# 04-POWERV2_4.net
KiCad netlist of a schematic drawn in Altium Designer
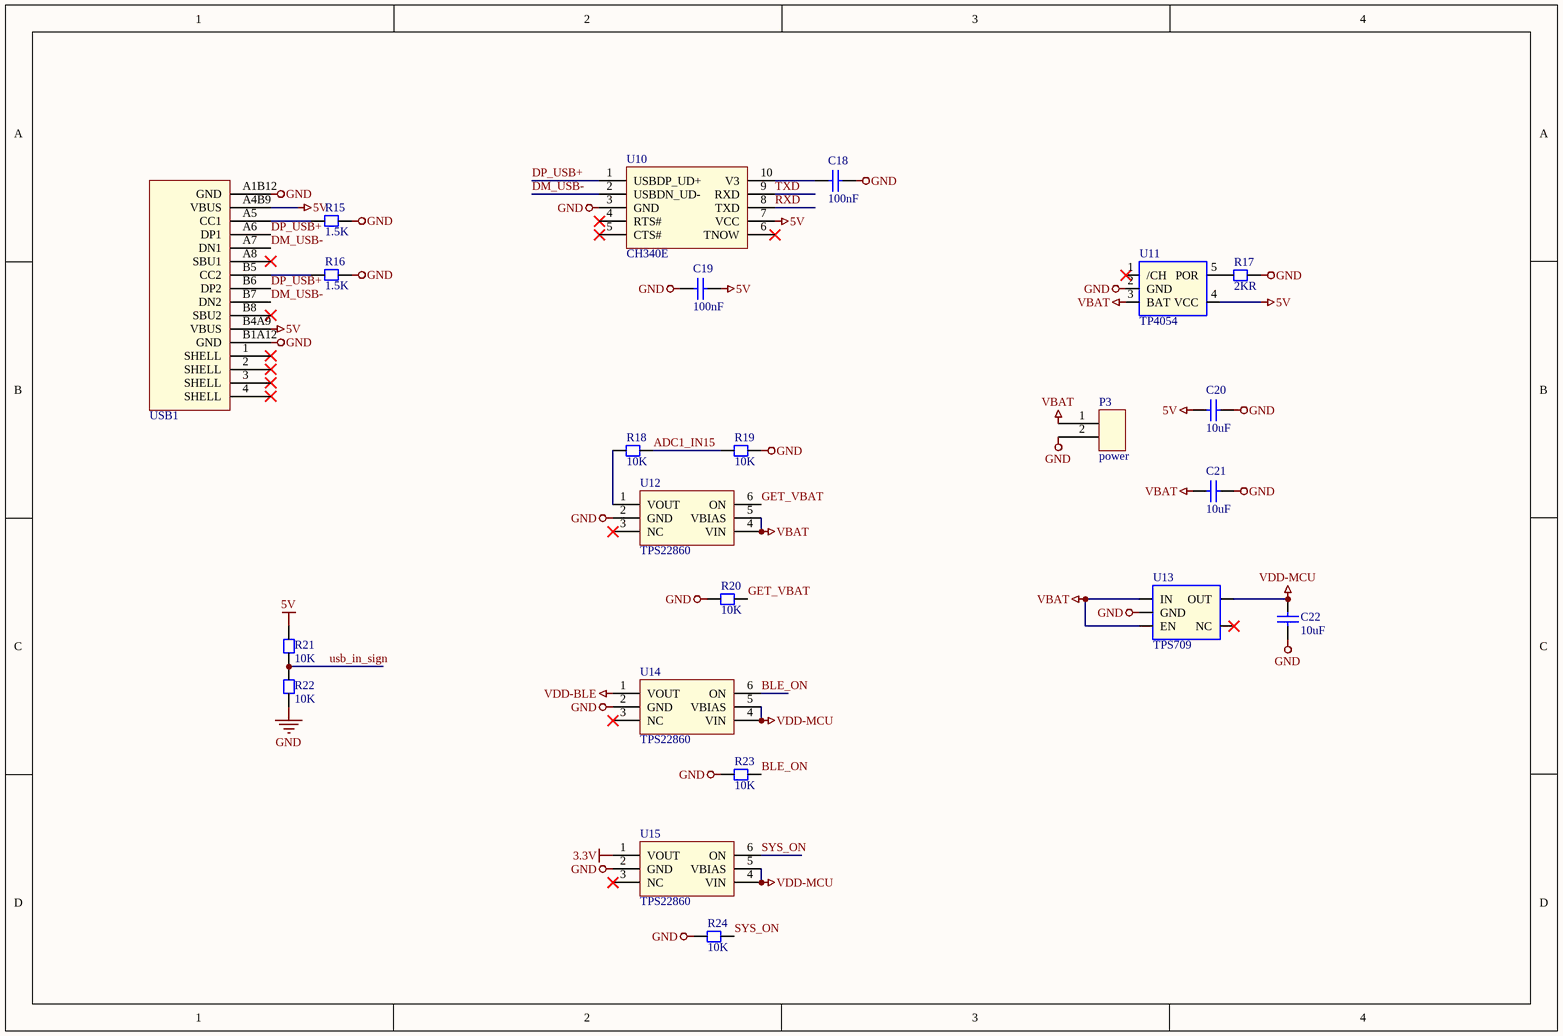
[diagram p0: 04-POWERV2.4.SchDoc]

(export (version "E")
  (design (tool "Eeschema 10.0.6"))
  (components
    (comp (ref "C18")
      (value "100nF")
      (footprint "CC1005-0402")
      (description "贴片电容")
      (libsource (lib "tianxiaohua_Schlib") (part "Chip capacitor"))
    )
    (comp (ref "C19")
      (value "100nF")
      (footprint "CC1005-0402")
      (description "贴片电容")
      (libsource (lib "tianxiaohua_Schlib") (part "Chip capacitor"))
    )
    (comp (ref "C20")
      (value "10uF")
      (footprint "CC1005-0402")
      (description "贴片电容")
      (libsource (lib "tianxiaohua_Schlib") (part "Chip capacitor"))
    )
    (comp (ref "C21")
      (value "10uF")
      (footprint "CC1005-0402")
      (description "贴片电容")
      (libsource (lib "tianxiaohua_Schlib") (part "Chip capacitor"))
    )
    (comp (ref "C22")
      (value "10uF")
      (footprint "CC1005-0402")
      (description "贴片电容")
      (libsource (lib "tianxiaohua_Schlib") (part "Chip capacitor"))
    )
    (comp (ref "P3")
      (value "power")
      (footprint "POWER-3.7V")
      (libsource (lib "tianxiaohua_Schlib") (part "power"))
    )
    (comp (ref "R15")
      (value "1.5K")
      (footprint "CR1005-0402")
      (description "贴片电阻")
      (libsource (lib "tianxiaohua_Schlib") (part "Chip resistor"))
    )
    (comp (ref "R16")
      (value "1.5K")
      (footprint "CR1005-0402")
      (description "贴片电阻")
      (libsource (lib "tianxiaohua_Schlib") (part "Chip resistor"))
    )
    (comp (ref "R17")
      (value "2KR")
      (footprint "CR1005-0402")
      (description "贴片电阻")
      (libsource (lib "tianxiaohua_Schlib") (part "Chip resistor"))
    )
    (comp (ref "R18")
      (value "10K")
      (footprint "CR1005-0402")
      (description "贴片电阻")
      (libsource (lib "tianxiaohua_Schlib") (part "Chip resistor"))
    )
    (comp (ref "R19")
      (value "10K")
      (footprint "CR1005-0402")
      (description "贴片电阻")
      (libsource (lib "") (part "Chip resistor_1"))
    )
    (comp (ref "R20")
      (value "10K")
      (footprint "CR1005-0402")
      (description "贴片电阻")
      (libsource (lib "") (part "Chip resistor_1"))
    )
    (comp (ref "R21")
      (value "10K")
      (footprint "CR1005-0402")
      (description "贴片电阻")
      (libsource (lib "") (part "Chip resistor_2"))
    )
    (comp (ref "R22")
      (value "10K")
      (footprint "CR1005-0402")
      (description "贴片电阻")
      (libsource (lib "") (part "Chip resistor_2"))
    )
    (comp (ref "R23")
      (value "10K")
      (footprint "CR1005-0402")
      (description "贴片电阻")
      (libsource (lib "") (part "Chip resistor_1"))
    )
    (comp (ref "R24")
      (value "10K")
      (footprint "CR1005-0402")
      (description "贴片电阻")
      (libsource (lib "") (part "Chip resistor_1"))
    )
    (comp (ref "U10")
      (value "CH340E")
      (footprint "MSOP-10")
      (description "usd转串口芯片 MSOP10封装")
      (libsource (lib "tianxiaohua_Schlib") (part "CH340E"))
    )
    (comp (ref "U11")
      (value "TP4054")
      (footprint "SOT23-5")
      (description "迷你充电IC SOT-23-5")
      (libsource (lib "tianxiaohua_Schlib") (part "TP4054"))
    )
    (comp (ref "U12")
      (value "TPS22860")
      (footprint "SOT23-6")
      (description "超低泄漏电流负载开关  超低泄漏电流负载开关 它可支持最大 200mA 的持续电\r流。 此开关可由一个打开/关闭输入 (ON) 控制")
      (libsource (lib "tianxiaohua_Schlib") (part "TPS22860"))
    )
    (comp (ref "U13")
      (value "TPS709")
      (footprint "SOT23-5")
      (description "3.3V降压IC SOT23-5封装 最大输出150ma电流")
      (libsource (lib "tianxiaohua_Schlib") (part "TPS709"))
    )
    (comp (ref "U14")
      (value "TPS22860")
      (footprint "SOT23-6")
      (description "超低泄漏电流负载开关  超低泄漏电流负载开关 它可支持最大 200mA 的持续电\r流。 此开关可由一个打开/关闭输入 (ON) 控制")
      (libsource (lib "tianxiaohua_Schlib") (part "TPS22860"))
    )
    (comp (ref "U15")
      (value "TPS22860")
      (footprint "SOT23-6")
      (description "超低泄漏电流负载开关  超低泄漏电流负载开关 它可支持最大 200mA 的持续电\r流。 此开关可由一个打开/关闭输入 (ON) 控制")
      (libsource (lib "tianxiaohua_Schlib") (part "TPS22860"))
    )
    (comp (ref "USB1")
      (value "Tpye-c 16P")
      (footprint "TYPE-C 16P")
      (description "16P 封装的TYPE -c接口 4固定插脚 双向")
      (libsource (lib "tianxiaohua_Schlib") (part "Tpye-c 16P"))
    )
  )
  (nets
    (net (code "1") (name "/ADC1_IN15") (class "Default")
      (node (ref "R18") (pin "1") (pinfunction "1_1") (pintype "passive"))
      (node (ref "R19") (pin "1") (pinfunction "1_1") (pintype "passive"))
    )
    (net (code "2") (name "/BLE_ON") (class "Default")
      (node (ref "R23") (pin "2") (pinfunction "2_2") (pintype "passive"))
      (node (ref "U14") (pin "6") (pinfunction "ON_6") (pintype "passive"))
    )
    (net (code "3") (name "/DM_USB-") (class "Default")
      (node (ref "U10") (pin "2") (pinfunction "USBDN_UD-_2") (pintype "passive"))
      (node (ref "USB1") (pin "A7") (pinfunction "DN1_A7") (pintype "power_in"))
      (node (ref "USB1") (pin "B7") (pinfunction "DN2_B7") (pintype "power_in"))
    )
    (net (code "4") (name "/DP_USB+") (class "Default")
      (node (ref "U10") (pin "1") (pinfunction "USBDP_UD+_1") (pintype "passive"))
      (node (ref "USB1") (pin "A6") (pinfunction "DP1_A6") (pintype "power_in"))
      (node (ref "USB1") (pin "B6") (pinfunction "DP2_B6") (pintype "power_in"))
    )
    (net (code "5") (name "/GET_VBAT") (class "Default")
      (node (ref "R20") (pin "2") (pinfunction "2_2") (pintype "passive"))
      (node (ref "U12") (pin "6") (pinfunction "ON_6") (pintype "passive"))
    )
    (net (code "6") (name "/RXD") (class "Default")
      (node (ref "U10") (pin "8") (pinfunction "TXD_8") (pintype "passive"))
    )
    (net (code "7") (name "/SYS_ON") (class "Default")
      (node (ref "R24") (pin "2") (pinfunction "2_2") (pintype "passive"))
      (node (ref "U15") (pin "6") (pinfunction "ON_6") (pintype "passive"))
    )
    (net (code "8") (name "/TXD") (class "Default")
      (node (ref "U10") (pin "9") (pinfunction "RXD_9") (pintype "passive"))
    )
    (net (code "9") (name "/usb_in_sign") (class "Default")
      (node (ref "R21") (pin "2") (pinfunction "2_2") (pintype "passive"))
      (node (ref "R22") (pin "1") (pinfunction "1_1") (pintype "passive"))
    )
    (net (code "10") (name "3.3V") (class "Default")
      (node (ref "U15") (pin "1") (pinfunction "VOUT_1") (pintype "passive"))
    )
    (net (code "11") (name "5V") (class "Default")
      (node (ref "C19") (pin "2") (pinfunction "2_2") (pintype "passive"))
      (node (ref "C20") (pin "2") (pinfunction "2_2") (pintype "passive"))
      (node (ref "R21") (pin "1") (pinfunction "1_1") (pintype "passive"))
      (node (ref "U10") (pin "7") (pinfunction "VCC_7") (pintype "passive"))
      (node (ref "U11") (pin "4") (pinfunction "VCC_4") (pintype "passive"))
      (node (ref "USB1") (pin "A4B9") (pinfunction "VBUS_A4B9") (pintype "power_in"))
      (node (ref "USB1") (pin "B4A9") (pinfunction "VBUS_B4A9") (pintype "power_in"))
    )
    (net (code "12") (name "GND") (class "Default")
      (node (ref "C18") (pin "2") (pinfunction "2_2") (pintype "passive"))
      (node (ref "C19") (pin "1") (pinfunction "1_1") (pintype "passive"))
      (node (ref "C20") (pin "1") (pinfunction "1_1") (pintype "passive"))
      (node (ref "C21") (pin "1") (pinfunction "1_1") (pintype "passive"))
      (node (ref "C22") (pin "2") (pinfunction "2_2") (pintype "passive"))
      (node (ref "P3") (pin "2") (pinfunction "2_2") (pintype "passive"))
      (node (ref "R15") (pin "1") (pinfunction "1_1") (pintype "passive"))
      (node (ref "R16") (pin "1") (pinfunction "1_1") (pintype "passive"))
      (node (ref "R17") (pin "1") (pinfunction "1_1") (pintype "passive"))
      (node (ref "R19") (pin "2") (pinfunction "2_2") (pintype "passive"))
      (node (ref "R20") (pin "1") (pinfunction "1_1") (pintype "passive"))
      (node (ref "R22") (pin "2") (pinfunction "2_2") (pintype "passive"))
      (node (ref "R23") (pin "1") (pinfunction "1_1") (pintype "passive"))
      (node (ref "R24") (pin "1") (pinfunction "1_1") (pintype "passive"))
      (node (ref "U10") (pin "3") (pinfunction "GND_3") (pintype "passive"))
      (node (ref "U11") (pin "2") (pinfunction "GND_2") (pintype "passive"))
      (node (ref "U12") (pin "2") (pinfunction "GND_2") (pintype "passive"))
      (node (ref "U13") (pin "2") (pinfunction "GND_2") (pintype "passive"))
      (node (ref "U14") (pin "2") (pinfunction "GND_2") (pintype "passive"))
      (node (ref "U15") (pin "2") (pinfunction "GND_2") (pintype "passive"))
      (node (ref "USB1") (pin "A1B12") (pinfunction "GND_A1B12") (pintype "power_in"))
      (node (ref "USB1") (pin "B1A12") (pinfunction "GND_B1A12") (pintype "power_in"))
    )
    (net (code "13") (name "Net-(U10-V3)") (class "Default")
      (node (ref "C18") (pin "1") (pinfunction "1_1") (pintype "passive"))
      (node (ref "U10") (pin "10") (pinfunction "V3_10") (pintype "passive"))
    )
    (net (code "14") (name "Net-(U11-POR)") (class "Default")
      (node (ref "R17") (pin "2") (pinfunction "2_2") (pintype "passive"))
      (node (ref "U11") (pin "5") (pinfunction "POR_5") (pintype "passive"))
    )
    (net (code "15") (name "Net-(U12-VOUT)") (class "Default")
      (node (ref "R18") (pin "2") (pinfunction "2_2") (pintype "passive"))
      (node (ref "U12") (pin "1") (pinfunction "VOUT_1") (pintype "passive"))
    )
    (net (code "16") (name "Net-(USB1-CC1)") (class "Default")
      (node (ref "R15") (pin "2") (pinfunction "2_2") (pintype "passive"))
      (node (ref "USB1") (pin "A5") (pinfunction "CC1_A5") (pintype "power_in"))
    )
    (net (code "17") (name "Net-(USB1-CC2)") (class "Default")
      (node (ref "R16") (pin "2") (pinfunction "2_2") (pintype "passive"))
      (node (ref "USB1") (pin "B5") (pinfunction "CC2_B5") (pintype "power_in"))
    )
    (net (code "18") (name "VBAT") (class "Default")
      (node (ref "C21") (pin "2") (pinfunction "2_2") (pintype "passive"))
      (node (ref "P3") (pin "1") (pinfunction "1_1") (pintype "passive"))
      (node (ref "U11") (pin "3") (pinfunction "BAT_3") (pintype "passive"))
      (node (ref "U12") (pin "4") (pinfunction "VIN_4") (pintype "passive"))
      (node (ref "U12") (pin "5") (pinfunction "VBIAS_5") (pintype "passive"))
      (node (ref "U13") (pin "1") (pinfunction "IN_1") (pintype "passive"))
      (node (ref "U13") (pin "3") (pinfunction "EN_3") (pintype "passive"))
    )
    (net (code "19") (name "VDD-BLE") (class "Default")
      (node (ref "U14") (pin "1") (pinfunction "VOUT_1") (pintype "passive"))
    )
    (net (code "20") (name "VDD-MCU") (class "Default")
      (node (ref "C22") (pin "1") (pinfunction "1_1") (pintype "passive"))
      (node (ref "U13") (pin "5") (pinfunction "OUT_5") (pintype "passive"))
      (node (ref "U14") (pin "4") (pinfunction "VIN_4") (pintype "passive"))
      (node (ref "U14") (pin "5") (pinfunction "VBIAS_5") (pintype "passive"))
      (node (ref "U15") (pin "4") (pinfunction "VIN_4") (pintype "passive"))
      (node (ref "U15") (pin "5") (pinfunction "VBIAS_5") (pintype "passive"))
    )
    (net (code "21") (name "unconnected-(U10-CTS#-Pad5)") (class "Default")
      (node (ref "U10") (pin "5") (pinfunction "CTS#_5") (pintype "passive+no_connect"))
    )
    (net (code "22") (name "unconnected-(U10-RTS#-Pad4)") (class "Default")
      (node (ref "U10") (pin "4") (pinfunction "RTS#_4") (pintype "passive+no_connect"))
    )
    (net (code "23") (name "unconnected-(U10-TNOW-Pad6)") (class "Default")
      (node (ref "U10") (pin "6") (pinfunction "TNOW_6") (pintype "passive+no_connect"))
    )
    (net (code "24") (name "unconnected-(U11-{slash}CH-Pad1)") (class "Default")
      (node (ref "U11") (pin "1") (pinfunction "/CH_1") (pintype "passive+no_connect"))
    )
    (net (code "25") (name "unconnected-(U12-NC-Pad3)") (class "Default")
      (node (ref "U12") (pin "3") (pinfunction "NC_3") (pintype "passive+no_connect"))
    )
    (net (code "26") (name "unconnected-(U13-NC-Pad4)") (class "Default")
      (node (ref "U13") (pin "4") (pinfunction "NC_4") (pintype "passive+no_connect"))
    )
    (net (code "27") (name "unconnected-(U14-NC-Pad3)") (class "Default")
      (node (ref "U14") (pin "3") (pinfunction "NC_3") (pintype "passive+no_connect"))
    )
    (net (code "28") (name "unconnected-(U15-NC-Pad3)") (class "Default")
      (node (ref "U15") (pin "3") (pinfunction "NC_3") (pintype "passive+no_connect"))
    )
    (net (code "29") (name "unconnected-(USB1-SBU1-PadA8)") (class "Default")
      (node (ref "USB1") (pin "A8") (pinfunction "SBU1_A8") (pintype "power_in+no_connect"))
    )
    (net (code "30") (name "unconnected-(USB1-SBU2-PadB8)") (class "Default")
      (node (ref "USB1") (pin "B8") (pinfunction "SBU2_B8") (pintype "power_in+no_connect"))
    )
    (net (code "31") (name "unconnected-(USB1-SHELL-Pad1)") (class "Default")
      (node (ref "USB1") (pin "1") (pinfunction "SHELL_1") (pintype "power_in+no_connect"))
    )
    (net (code "32") (name "unconnected-(USB1-SHELL-Pad2)") (class "Default")
      (node (ref "USB1") (pin "2") (pinfunction "SHELL_2") (pintype "power_in+no_connect"))
    )
    (net (code "33") (name "unconnected-(USB1-SHELL-Pad3)") (class "Default")
      (node (ref "USB1") (pin "3") (pinfunction "SHELL_3") (pintype "power_in+no_connect"))
    )
    (net (code "34") (name "unconnected-(USB1-SHELL-Pad4)") (class "Default")
      (node (ref "USB1") (pin "4") (pinfunction "SHELL_4") (pintype "power_in+no_connect"))
    )
  )
)
